# 2MB_Simplified.net
KiCad netlist of a schematic drawn in EAGLE
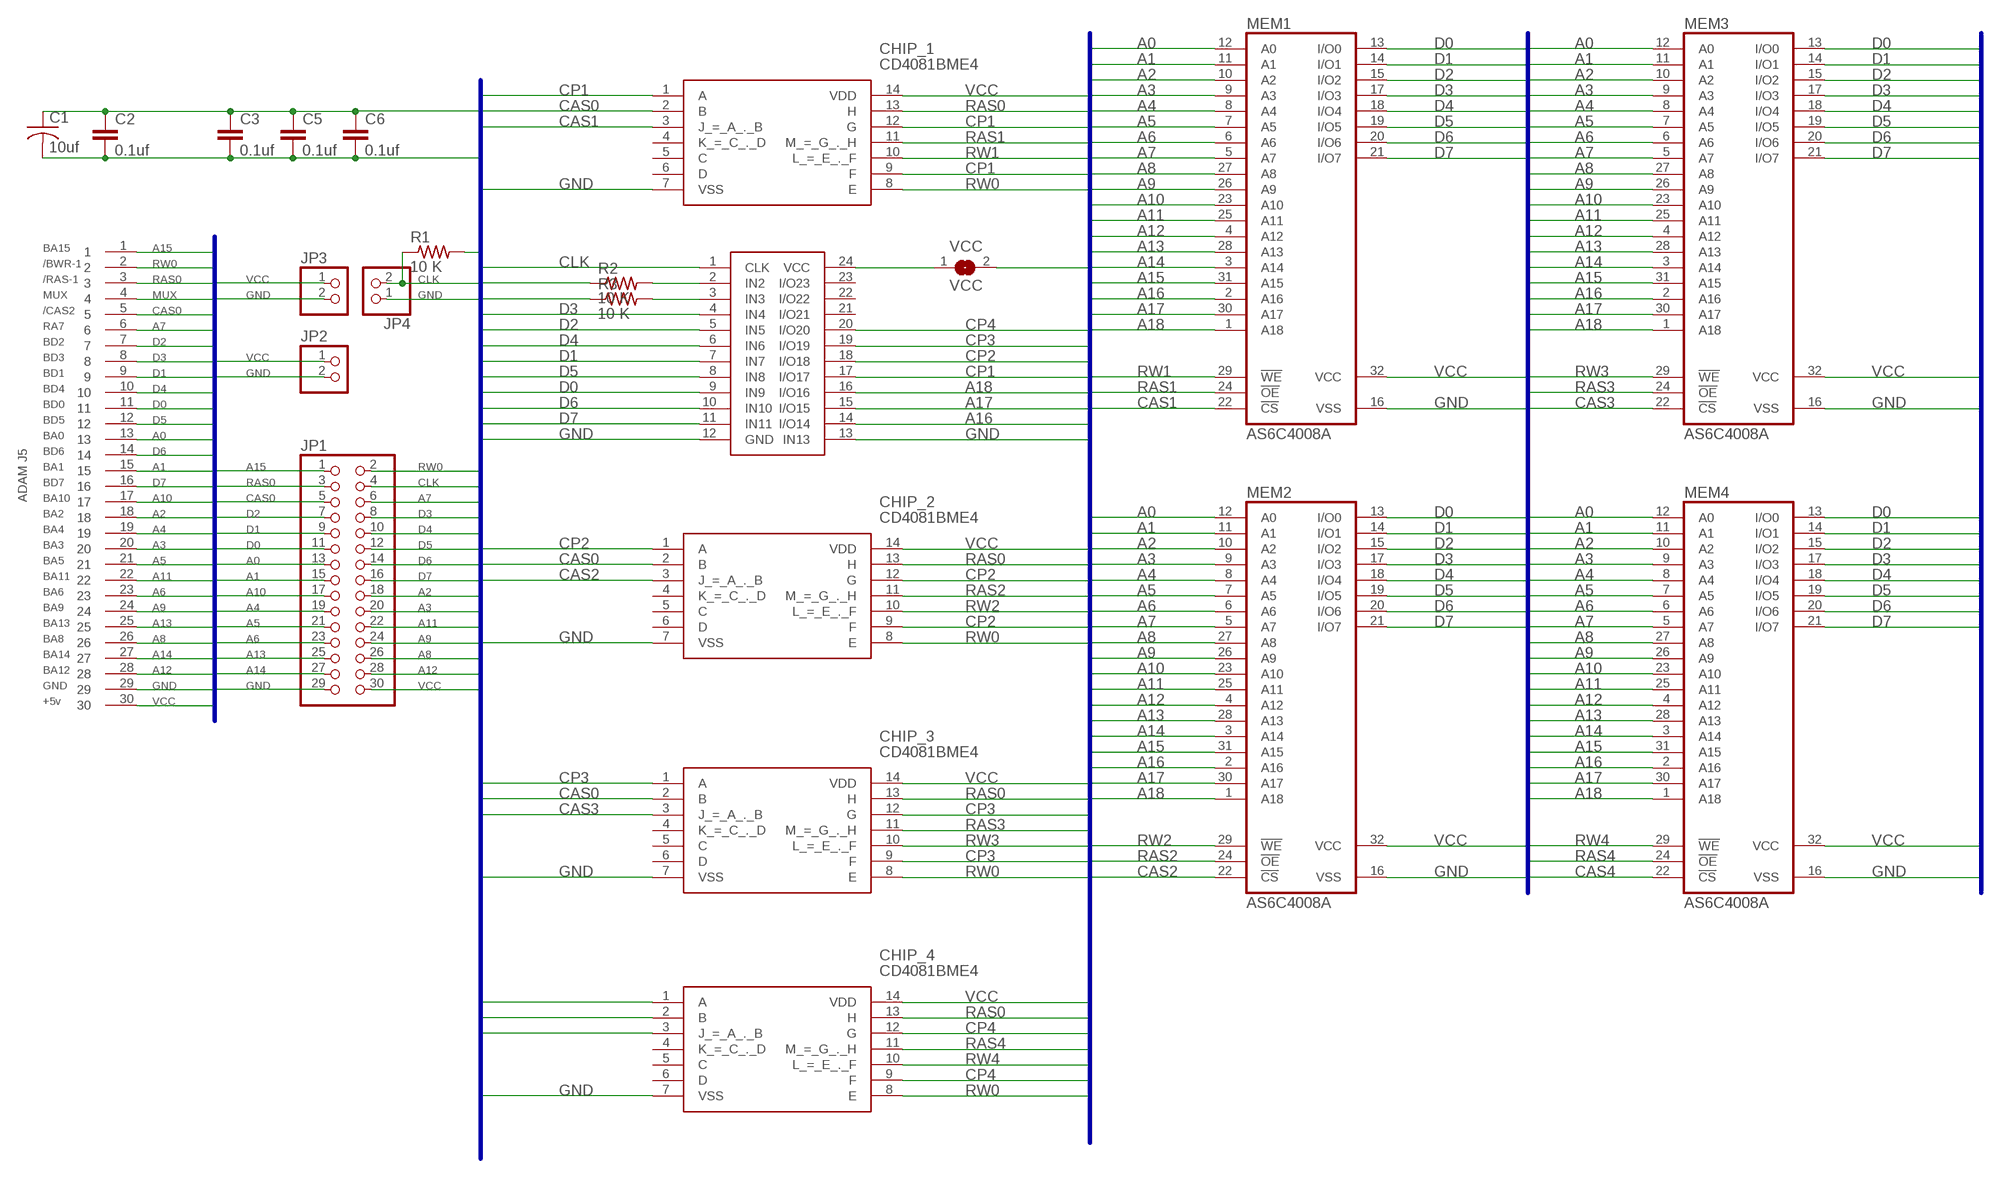
[diagram p0: schematic, sheet 1]

(export (version "E")
  (design (tool "Eeschema 10.0.6"))
  (components
    (comp (ref "C1")
      (value "10uf")
      (footprint "eagle-import:C050-025X075")
      (libsource (lib "eagle-import") (part "C-US050-025X075"))
    )
    (comp (ref "C2")
      (value "0.1uf")
      (footprint "eagle-import:C1206")
      (libsource (lib "eagle-import") (part "C-EUC1206"))
    )
    (comp (ref "C3")
      (value "0.1uf")
      (footprint "eagle-import:C1206")
      (libsource (lib "eagle-import") (part "C-EUC1206"))
    )
    (comp (ref "C5")
      (value "0.1uf")
      (footprint "eagle-import:C1206")
      (libsource (lib "eagle-import") (part "C-EUC1206"))
    )
    (comp (ref "C6")
      (value "0.1uf")
      (footprint "eagle-import:C1206")
      (libsource (lib "eagle-import") (part "C-EUC1206"))
    )
    (comp (ref "CHIP_1")
      (value "CD4081BME4")
      (footprint "eagle-import:SOIC127P600X175-14N")
      (fields (field (name "MOUSER_PART_NUMBER") "595-CD4081BME4"))
      (libsource (lib "eagle-import") (part "CD4081BME4"))
    )
    (comp (ref "CHIP_2")
      (value "CD4081BME4")
      (footprint "eagle-import:SOIC127P600X175-14N")
      (fields (field (name "MOUSER_PART_NUMBER") "595-CD4081BME4"))
      (libsource (lib "eagle-import") (part "CD4081BME4"))
    )
    (comp (ref "CHIP_3")
      (value "CD4081BME4")
      (footprint "eagle-import:SOIC127P600X175-14N")
      (fields (field (name "MOUSER_PART_NUMBER") "595-CD4081BME4"))
      (libsource (lib "eagle-import") (part "CD4081BME4"))
    )
    (comp (ref "CHIP_4")
      (value "CD4081BME4")
      (footprint "eagle-import:SOIC127P600X175-14N")
      (fields (field (name "MOUSER_PART_NUMBER") "595-CD4081BME4"))
      (libsource (lib "eagle-import") (part "CD4081BME4"))
    )
    (comp (ref "JP1")
      (value "PINHD-2X15")
      (footprint "eagle-import:2X15")
      (libsource (lib "eagle-import") (part "PINHD-2X15"))
    )
    (comp (ref "JP2")
      (value "PINHD-1X2")
      (footprint "eagle-import:1X02")
      (libsource (lib "eagle-import") (part "PINHD-1X2"))
    )
    (comp (ref "JP3")
      (value "PINHD-1X2")
      (footprint "eagle-import:1X02")
      (libsource (lib "eagle-import") (part "PINHD-1X2"))
    )
    (comp (ref "JP4")
      (value "PINHD-1X2")
      (footprint "eagle-import:1X02")
      (libsource (lib "eagle-import") (part "PINHD-1X2"))
    )
    (comp (ref "MEM1")
      (value "AS6C4008A")
      (footprint "eagle-import:SOP32-V2")
      (libsource (lib "eagle-import") (part "AS6C4008A"))
    )
    (comp (ref "MEM2")
      (value "AS6C4008A")
      (footprint "eagle-import:SOP32-V2")
      (libsource (lib "eagle-import") (part "AS6C4008A"))
    )
    (comp (ref "MEM3")
      (value "AS6C4008A")
      (footprint "eagle-import:SOP32-V2")
      (libsource (lib "eagle-import") (part "AS6C4008A"))
    )
    (comp (ref "MEM4")
      (value "AS6C4008A")
      (footprint "eagle-import:SOP32-V2")
      (libsource (lib "eagle-import") (part "AS6C4008A"))
    )
    (comp (ref "R1")
      (value "10 K")
      (footprint "eagle-import:M1206")
      (libsource (lib "eagle-import") (part "R-US_M1206"))
    )
    (comp (ref "R2")
      (value "10 K")
      (footprint "eagle-import:M1206")
      (libsource (lib "eagle-import") (part "R-US_M1206"))
    )
    (comp (ref "R3")
      (value "10 K")
      (footprint "eagle-import:M1206")
      (libsource (lib "eagle-import") (part "R-US_M1206"))
    )
    (comp (ref "U$3")
      (value "J5CARD")
      (footprint "eagle-import:J5CARD")
      (libsource (lib "eagle-import") (part "J5CARD"))
    )
    (comp (ref "U$6")
      (value "ATF22V10")
      (footprint "eagle-import:SO24W")
      (libsource (lib "eagle-import") (part "ATF22V10"))
    )
    (comp (ref "VCC")
      (value "VCC")
      (footprint "eagle-import:SJ")
      (libsource (lib "eagle-import") (part "SJ"))
    )
  )
  (nets
    (net (code "1") (name "/A0") (class "Default")
      (node (ref "JP1") (pin "13") (pinfunction "13_13") (pintype "passive"))
      (node (ref "MEM1") (pin "12") (pinfunction "A0_12") (pintype "input"))
      (node (ref "MEM2") (pin "12") (pinfunction "A0_12") (pintype "input"))
      (node (ref "MEM3") (pin "12") (pinfunction "A0_12") (pintype "input"))
      (node (ref "MEM4") (pin "12") (pinfunction "A0_12") (pintype "input"))
      (node (ref "U$3") (pin "13") (pinfunction "13_13") (pintype "bidirectional"))
    )
    (net (code "2") (name "/A1") (class "Default")
      (node (ref "JP1") (pin "15") (pinfunction "15_15") (pintype "passive"))
      (node (ref "MEM1") (pin "11") (pinfunction "A1_11") (pintype "input"))
      (node (ref "MEM2") (pin "11") (pinfunction "A1_11") (pintype "input"))
      (node (ref "MEM3") (pin "11") (pinfunction "A1_11") (pintype "input"))
      (node (ref "MEM4") (pin "11") (pinfunction "A1_11") (pintype "input"))
      (node (ref "U$3") (pin "15") (pinfunction "15_15") (pintype "bidirectional"))
    )
    (net (code "3") (name "/A2") (class "Default")
      (node (ref "JP1") (pin "18") (pinfunction "18_18") (pintype "passive"))
      (node (ref "MEM1") (pin "10") (pinfunction "A2_10") (pintype "input"))
      (node (ref "MEM2") (pin "10") (pinfunction "A2_10") (pintype "input"))
      (node (ref "MEM3") (pin "10") (pinfunction "A2_10") (pintype "input"))
      (node (ref "MEM4") (pin "10") (pinfunction "A2_10") (pintype "input"))
      (node (ref "U$3") (pin "18") (pinfunction "18_18") (pintype "bidirectional"))
    )
    (net (code "4") (name "/A3") (class "Default")
      (node (ref "JP1") (pin "20") (pinfunction "20_20") (pintype "passive"))
      (node (ref "MEM1") (pin "9") (pinfunction "A3_9") (pintype "input"))
      (node (ref "MEM2") (pin "9") (pinfunction "A3_9") (pintype "input"))
      (node (ref "MEM3") (pin "9") (pinfunction "A3_9") (pintype "input"))
      (node (ref "MEM4") (pin "9") (pinfunction "A3_9") (pintype "input"))
      (node (ref "U$3") (pin "20") (pinfunction "20_20") (pintype "bidirectional"))
    )
    (net (code "5") (name "/A4") (class "Default")
      (node (ref "JP1") (pin "19") (pinfunction "19_19") (pintype "passive"))
      (node (ref "MEM1") (pin "8") (pinfunction "A4_8") (pintype "input"))
      (node (ref "MEM2") (pin "8") (pinfunction "A4_8") (pintype "input"))
      (node (ref "MEM3") (pin "8") (pinfunction "A4_8") (pintype "input"))
      (node (ref "MEM4") (pin "8") (pinfunction "A4_8") (pintype "input"))
      (node (ref "U$3") (pin "19") (pinfunction "19_19") (pintype "bidirectional"))
    )
    (net (code "6") (name "/A5") (class "Default")
      (node (ref "JP1") (pin "21") (pinfunction "21_21") (pintype "passive"))
      (node (ref "MEM1") (pin "7") (pinfunction "A5_7") (pintype "input"))
      (node (ref "MEM2") (pin "7") (pinfunction "A5_7") (pintype "input"))
      (node (ref "MEM3") (pin "7") (pinfunction "A5_7") (pintype "input"))
      (node (ref "MEM4") (pin "7") (pinfunction "A5_7") (pintype "input"))
      (node (ref "U$3") (pin "21") (pinfunction "21_21") (pintype "bidirectional"))
    )
    (net (code "7") (name "/A6") (class "Default")
      (node (ref "JP1") (pin "23") (pinfunction "23_23") (pintype "passive"))
      (node (ref "MEM1") (pin "6") (pinfunction "A6_6") (pintype "input"))
      (node (ref "MEM2") (pin "6") (pinfunction "A6_6") (pintype "input"))
      (node (ref "MEM3") (pin "6") (pinfunction "A6_6") (pintype "input"))
      (node (ref "MEM4") (pin "6") (pinfunction "A6_6") (pintype "input"))
      (node (ref "U$3") (pin "23") (pinfunction "23_23") (pintype "bidirectional"))
    )
    (net (code "8") (name "/A7") (class "Default")
      (node (ref "JP1") (pin "6") (pinfunction "6_6") (pintype "passive"))
      (node (ref "MEM1") (pin "5") (pinfunction "A7_5") (pintype "input"))
      (node (ref "MEM2") (pin "5") (pinfunction "A7_5") (pintype "input"))
      (node (ref "MEM3") (pin "5") (pinfunction "A7_5") (pintype "input"))
      (node (ref "MEM4") (pin "5") (pinfunction "A7_5") (pintype "input"))
      (node (ref "U$3") (pin "6") (pinfunction "6_6") (pintype "bidirectional"))
    )
    (net (code "9") (name "/A8") (class "Default")
      (node (ref "JP1") (pin "26") (pinfunction "26_26") (pintype "passive"))
      (node (ref "MEM1") (pin "27") (pinfunction "A8_27") (pintype "input"))
      (node (ref "MEM2") (pin "27") (pinfunction "A8_27") (pintype "input"))
      (node (ref "MEM3") (pin "27") (pinfunction "A8_27") (pintype "input"))
      (node (ref "MEM4") (pin "27") (pinfunction "A8_27") (pintype "input"))
      (node (ref "U$3") (pin "26") (pinfunction "26_26") (pintype "bidirectional"))
    )
    (net (code "10") (name "/A9") (class "Default")
      (node (ref "JP1") (pin "24") (pinfunction "24_24") (pintype "passive"))
      (node (ref "MEM1") (pin "26") (pinfunction "A9_26") (pintype "input"))
      (node (ref "MEM2") (pin "26") (pinfunction "A9_26") (pintype "input"))
      (node (ref "MEM3") (pin "26") (pinfunction "A9_26") (pintype "input"))
      (node (ref "MEM4") (pin "26") (pinfunction "A9_26") (pintype "input"))
      (node (ref "U$3") (pin "24") (pinfunction "24_24") (pintype "bidirectional"))
    )
    (net (code "11") (name "/A10") (class "Default")
      (node (ref "JP1") (pin "17") (pinfunction "17_17") (pintype "passive"))
      (node (ref "MEM1") (pin "23") (pinfunction "A10_23") (pintype "input"))
      (node (ref "MEM2") (pin "23") (pinfunction "A10_23") (pintype "input"))
      (node (ref "MEM3") (pin "23") (pinfunction "A10_23") (pintype "input"))
      (node (ref "MEM4") (pin "23") (pinfunction "A10_23") (pintype "input"))
      (node (ref "U$3") (pin "17") (pinfunction "17_17") (pintype "bidirectional"))
    )
    (net (code "12") (name "/A11") (class "Default")
      (node (ref "JP1") (pin "22") (pinfunction "22_22") (pintype "passive"))
      (node (ref "MEM1") (pin "25") (pinfunction "A11_25") (pintype "input"))
      (node (ref "MEM2") (pin "25") (pinfunction "A11_25") (pintype "input"))
      (node (ref "MEM3") (pin "25") (pinfunction "A11_25") (pintype "input"))
      (node (ref "MEM4") (pin "25") (pinfunction "A11_25") (pintype "input"))
      (node (ref "U$3") (pin "22") (pinfunction "22_22") (pintype "bidirectional"))
    )
    (net (code "13") (name "/A12") (class "Default")
      (node (ref "JP1") (pin "28") (pinfunction "28_28") (pintype "passive"))
      (node (ref "MEM1") (pin "4") (pinfunction "A12_4") (pintype "input"))
      (node (ref "MEM2") (pin "4") (pinfunction "A12_4") (pintype "input"))
      (node (ref "MEM3") (pin "4") (pinfunction "A12_4") (pintype "input"))
      (node (ref "MEM4") (pin "4") (pinfunction "A12_4") (pintype "input"))
      (node (ref "U$3") (pin "28") (pinfunction "28_28") (pintype "bidirectional"))
    )
    (net (code "14") (name "/A13") (class "Default")
      (node (ref "JP1") (pin "25") (pinfunction "25_25") (pintype "passive"))
      (node (ref "MEM1") (pin "28") (pinfunction "A13_28") (pintype "input"))
      (node (ref "MEM2") (pin "28") (pinfunction "A13_28") (pintype "input"))
      (node (ref "MEM3") (pin "28") (pinfunction "A13_28") (pintype "input"))
      (node (ref "MEM4") (pin "28") (pinfunction "A13_28") (pintype "input"))
      (node (ref "U$3") (pin "25") (pinfunction "25_25") (pintype "bidirectional"))
    )
    (net (code "15") (name "/A14") (class "Default")
      (node (ref "JP1") (pin "27") (pinfunction "27_27") (pintype "passive"))
      (node (ref "MEM1") (pin "3") (pinfunction "A14_3") (pintype "input"))
      (node (ref "MEM2") (pin "3") (pinfunction "A14_3") (pintype "input"))
      (node (ref "MEM3") (pin "3") (pinfunction "A14_3") (pintype "input"))
      (node (ref "MEM4") (pin "3") (pinfunction "A14_3") (pintype "input"))
      (node (ref "U$3") (pin "27") (pinfunction "27_27") (pintype "bidirectional"))
    )
    (net (code "16") (name "/A15") (class "Default")
      (node (ref "JP1") (pin "1") (pinfunction "1_1") (pintype "passive"))
      (node (ref "MEM1") (pin "31") (pinfunction "A15_31") (pintype "input"))
      (node (ref "MEM2") (pin "31") (pinfunction "A15_31") (pintype "input"))
      (node (ref "MEM3") (pin "31") (pinfunction "A15_31") (pintype "input"))
      (node (ref "MEM4") (pin "31") (pinfunction "A15_31") (pintype "input"))
      (node (ref "U$3") (pin "1") (pinfunction "1_1") (pintype "bidirectional"))
    )
    (net (code "17") (name "/A16") (class "Default")
      (node (ref "MEM1") (pin "2") (pinfunction "A16_2") (pintype "input"))
      (node (ref "MEM2") (pin "2") (pinfunction "A16_2") (pintype "input"))
      (node (ref "MEM3") (pin "2") (pinfunction "A16_2") (pintype "input"))
      (node (ref "MEM4") (pin "2") (pinfunction "A16_2") (pintype "input"))
      (node (ref "U$6") (pin "14") (pinfunction "I/O14_14") (pintype "bidirectional"))
    )
    (net (code "18") (name "/A17") (class "Default")
      (node (ref "MEM1") (pin "30") (pinfunction "A17_30") (pintype "input"))
      (node (ref "MEM2") (pin "30") (pinfunction "A17_30") (pintype "input"))
      (node (ref "MEM3") (pin "30") (pinfunction "A17_30") (pintype "input"))
      (node (ref "MEM4") (pin "30") (pinfunction "A17_30") (pintype "input"))
      (node (ref "U$6") (pin "15") (pinfunction "I/O15_15") (pintype "bidirectional"))
    )
    (net (code "19") (name "/A18") (class "Default")
      (node (ref "MEM1") (pin "1") (pinfunction "A18_1") (pintype "input"))
      (node (ref "MEM2") (pin "1") (pinfunction "A18_1") (pintype "input"))
      (node (ref "MEM3") (pin "1") (pinfunction "A18_1") (pintype "input"))
      (node (ref "MEM4") (pin "1") (pinfunction "A18_1") (pintype "input"))
      (node (ref "U$6") (pin "16") (pinfunction "I/O16_16") (pintype "bidirectional"))
    )
    (net (code "20") (name "/CAS0") (class "Default")
      (node (ref "CHIP_1") (pin "2") (pinfunction "B_2") (pintype "bidirectional"))
      (node (ref "CHIP_2") (pin "2") (pinfunction "B_2") (pintype "bidirectional"))
      (node (ref "CHIP_3") (pin "2") (pinfunction "B_2") (pintype "bidirectional"))
      (node (ref "CHIP_4") (pin "2") (pinfunction "B_2") (pintype "bidirectional"))
      (node (ref "JP1") (pin "5") (pinfunction "5_5") (pintype "passive"))
      (node (ref "U$3") (pin "5") (pinfunction "5_5") (pintype "bidirectional"))
    )
    (net (code "21") (name "/CAS1") (class "Default")
      (node (ref "CHIP_1") (pin "3") (pinfunction "J_=_A_._B_3") (pintype "bidirectional"))
      (node (ref "MEM1") (pin "22") (pinfunction "~{CS}_22") (pintype "input"))
    )
    (net (code "22") (name "/CAS2") (class "Default")
      (node (ref "CHIP_2") (pin "3") (pinfunction "J_=_A_._B_3") (pintype "bidirectional"))
      (node (ref "MEM2") (pin "22") (pinfunction "~{CS}_22") (pintype "input"))
    )
    (net (code "23") (name "/CAS3") (class "Default")
      (node (ref "CHIP_3") (pin "3") (pinfunction "J_=_A_._B_3") (pintype "bidirectional"))
      (node (ref "MEM3") (pin "22") (pinfunction "~{CS}_22") (pintype "input"))
    )
    (net (code "24") (name "/CAS4") (class "Default")
      (node (ref "CHIP_4") (pin "3") (pinfunction "J_=_A_._B_3") (pintype "bidirectional"))
      (node (ref "MEM4") (pin "22") (pinfunction "~{CS}_22") (pintype "input"))
    )
    (net (code "25") (name "/CLK") (class "Default")
      (node (ref "JP1") (pin "4") (pinfunction "4_4") (pintype "passive"))
      (node (ref "JP4") (pin "2") (pinfunction "2_2") (pintype "passive"))
      (node (ref "R1") (pin "1") (pinfunction "1_1") (pintype "passive"))
      (node (ref "U$6") (pin "1") (pinfunction "CLK_1") (pintype "bidirectional"))
    )
    (net (code "26") (name "/CP1") (class "Default")
      (node (ref "CHIP_1") (pin "1") (pinfunction "A_1") (pintype "bidirectional"))
      (node (ref "CHIP_1") (pin "12") (pinfunction "G_12") (pintype "bidirectional"))
      (node (ref "CHIP_1") (pin "9") (pinfunction "F_9") (pintype "bidirectional"))
      (node (ref "U$6") (pin "17") (pinfunction "I/O17_17") (pintype "bidirectional"))
    )
    (net (code "27") (name "/CP2") (class "Default")
      (node (ref "CHIP_2") (pin "1") (pinfunction "A_1") (pintype "bidirectional"))
      (node (ref "CHIP_2") (pin "12") (pinfunction "G_12") (pintype "bidirectional"))
      (node (ref "CHIP_2") (pin "9") (pinfunction "F_9") (pintype "bidirectional"))
      (node (ref "U$6") (pin "18") (pinfunction "I/O18_18") (pintype "bidirectional"))
    )
    (net (code "28") (name "/CP3") (class "Default")
      (node (ref "CHIP_3") (pin "1") (pinfunction "A_1") (pintype "bidirectional"))
      (node (ref "CHIP_3") (pin "12") (pinfunction "G_12") (pintype "bidirectional"))
      (node (ref "CHIP_3") (pin "9") (pinfunction "F_9") (pintype "bidirectional"))
      (node (ref "U$6") (pin "19") (pinfunction "I/O19_19") (pintype "bidirectional"))
    )
    (net (code "29") (name "/CP4") (class "Default")
      (node (ref "CHIP_4") (pin "1") (pinfunction "A_1") (pintype "bidirectional"))
      (node (ref "CHIP_4") (pin "12") (pinfunction "G_12") (pintype "bidirectional"))
      (node (ref "CHIP_4") (pin "9") (pinfunction "F_9") (pintype "bidirectional"))
      (node (ref "U$6") (pin "20") (pinfunction "I/O20_20") (pintype "bidirectional"))
    )
    (net (code "30") (name "/D0") (class "Default")
      (node (ref "JP1") (pin "11") (pinfunction "11_11") (pintype "passive"))
      (node (ref "MEM1") (pin "13") (pinfunction "I/O0_13") (pintype "bidirectional"))
      (node (ref "MEM2") (pin "13") (pinfunction "I/O0_13") (pintype "bidirectional"))
      (node (ref "MEM3") (pin "13") (pinfunction "I/O0_13") (pintype "bidirectional"))
      (node (ref "MEM4") (pin "13") (pinfunction "I/O0_13") (pintype "bidirectional"))
      (node (ref "U$3") (pin "11") (pinfunction "11_11") (pintype "bidirectional"))
      (node (ref "U$6") (pin "9") (pinfunction "IN9_9") (pintype "bidirectional"))
    )
    (net (code "31") (name "/D1") (class "Default")
      (node (ref "JP1") (pin "9") (pinfunction "9_9") (pintype "passive"))
      (node (ref "MEM1") (pin "14") (pinfunction "I/O1_14") (pintype "bidirectional"))
      (node (ref "MEM2") (pin "14") (pinfunction "I/O1_14") (pintype "bidirectional"))
      (node (ref "MEM3") (pin "14") (pinfunction "I/O1_14") (pintype "bidirectional"))
      (node (ref "MEM4") (pin "14") (pinfunction "I/O1_14") (pintype "bidirectional"))
      (node (ref "U$3") (pin "9") (pinfunction "9_9") (pintype "bidirectional"))
      (node (ref "U$6") (pin "7") (pinfunction "IN7_7") (pintype "bidirectional"))
    )
    (net (code "32") (name "/D2") (class "Default")
      (node (ref "JP1") (pin "7") (pinfunction "7_7") (pintype "passive"))
      (node (ref "MEM1") (pin "15") (pinfunction "I/O2_15") (pintype "bidirectional"))
      (node (ref "MEM2") (pin "15") (pinfunction "I/O2_15") (pintype "bidirectional"))
      (node (ref "MEM3") (pin "15") (pinfunction "I/O2_15") (pintype "bidirectional"))
      (node (ref "MEM4") (pin "15") (pinfunction "I/O2_15") (pintype "bidirectional"))
      (node (ref "U$3") (pin "7") (pinfunction "7_7") (pintype "bidirectional"))
      (node (ref "U$6") (pin "5") (pinfunction "IN5_5") (pintype "bidirectional"))
    )
    (net (code "33") (name "/D3") (class "Default")
      (node (ref "JP1") (pin "8") (pinfunction "8_8") (pintype "passive"))
      (node (ref "MEM1") (pin "17") (pinfunction "I/O3_17") (pintype "bidirectional"))
      (node (ref "MEM2") (pin "17") (pinfunction "I/O3_17") (pintype "bidirectional"))
      (node (ref "MEM3") (pin "17") (pinfunction "I/O3_17") (pintype "bidirectional"))
      (node (ref "MEM4") (pin "17") (pinfunction "I/O3_17") (pintype "bidirectional"))
      (node (ref "U$3") (pin "8") (pinfunction "8_8") (pintype "bidirectional"))
      (node (ref "U$6") (pin "4") (pinfunction "IN4_4") (pintype "bidirectional"))
    )
    (net (code "34") (name "/D4") (class "Default")
      (node (ref "JP1") (pin "10") (pinfunction "10_10") (pintype "passive"))
      (node (ref "MEM1") (pin "18") (pinfunction "I/O4_18") (pintype "bidirectional"))
      (node (ref "MEM2") (pin "18") (pinfunction "I/O4_18") (pintype "bidirectional"))
      (node (ref "MEM3") (pin "18") (pinfunction "I/O4_18") (pintype "bidirectional"))
      (node (ref "MEM4") (pin "18") (pinfunction "I/O4_18") (pintype "bidirectional"))
      (node (ref "U$3") (pin "10") (pinfunction "10_10") (pintype "bidirectional"))
      (node (ref "U$6") (pin "6") (pinfunction "IN6_6") (pintype "bidirectional"))
    )
    (net (code "35") (name "/D5") (class "Default")
      (node (ref "JP1") (pin "12") (pinfunction "12_12") (pintype "passive"))
      (node (ref "MEM1") (pin "19") (pinfunction "I/O5_19") (pintype "bidirectional"))
      (node (ref "MEM2") (pin "19") (pinfunction "I/O5_19") (pintype "bidirectional"))
      (node (ref "MEM3") (pin "19") (pinfunction "I/O5_19") (pintype "bidirectional"))
      (node (ref "MEM4") (pin "19") (pinfunction "I/O5_19") (pintype "bidirectional"))
      (node (ref "U$3") (pin "12") (pinfunction "12_12") (pintype "bidirectional"))
      (node (ref "U$6") (pin "8") (pinfunction "IN8_8") (pintype "bidirectional"))
    )
    (net (code "36") (name "/D6") (class "Default")
      (node (ref "JP1") (pin "14") (pinfunction "14_14") (pintype "passive"))
      (node (ref "MEM1") (pin "20") (pinfunction "I/O6_20") (pintype "bidirectional"))
      (node (ref "MEM2") (pin "20") (pinfunction "I/O6_20") (pintype "bidirectional"))
      (node (ref "MEM3") (pin "20") (pinfunction "I/O6_20") (pintype "bidirectional"))
      (node (ref "MEM4") (pin "20") (pinfunction "I/O6_20") (pintype "bidirectional"))
      (node (ref "U$3") (pin "14") (pinfunction "14_14") (pintype "bidirectional"))
      (node (ref "U$6") (pin "10") (pinfunction "IN10_10") (pintype "bidirectional"))
    )
    (net (code "37") (name "/D7") (class "Default")
      (node (ref "JP1") (pin "16") (pinfunction "16_16") (pintype "passive"))
      (node (ref "MEM1") (pin "21") (pinfunction "I/O7_21") (pintype "bidirectional"))
      (node (ref "MEM2") (pin "21") (pinfunction "I/O7_21") (pintype "bidirectional"))
      (node (ref "MEM3") (pin "21") (pinfunction "I/O7_21") (pintype "bidirectional"))
      (node (ref "MEM4") (pin "21") (pinfunction "I/O7_21") (pintype "bidirectional"))
      (node (ref "U$3") (pin "16") (pinfunction "16_16") (pintype "bidirectional"))
      (node (ref "U$6") (pin "11") (pinfunction "IN11_11") (pintype "bidirectional"))
    )
    (net (code "38") (name "/GND") (class "Default")
      (node (ref "C1") (pin "2") (pinfunction "2_2") (pintype "passive"))
      (node (ref "C2") (pin "2") (pinfunction "2_2") (pintype "passive"))
      (node (ref "C3") (pin "2") (pinfunction "2_2") (pintype "passive"))
      (node (ref "C5") (pin "2") (pinfunction "2_2") (pintype "passive"))
      (node (ref "C6") (pin "2") (pinfunction "2_2") (pintype "passive"))
      (node (ref "CHIP_1") (pin "7") (pinfunction "VSS_7") (pintype "bidirectional"))
      (node (ref "CHIP_2") (pin "7") (pinfunction "VSS_7") (pintype "bidirectional"))
      (node (ref "CHIP_3") (pin "7") (pinfunction "VSS_7") (pintype "bidirectional"))
      (node (ref "CHIP_4") (pin "7") (pinfunction "VSS_7") (pintype "bidirectional"))
      (node (ref "JP1") (pin "29") (pinfunction "29_29") (pintype "passive"))
      (node (ref "JP2") (pin "2") (pinfunction "2_2") (pintype "passive"))
      (node (ref "JP3") (pin "2") (pinfunction "2_2") (pintype "passive"))
      (node (ref "JP4") (pin "1") (pinfunction "1_1") (pintype "passive"))
      (node (ref "MEM1") (pin "16") (pinfunction "VSS_16") (pintype "power_in"))
      (node (ref "MEM2") (pin "16") (pinfunction "VSS_16") (pintype "power_in"))
      (node (ref "MEM3") (pin "16") (pinfunction "VSS_16") (pintype "power_in"))
      (node (ref "MEM4") (pin "16") (pinfunction "VSS_16") (pintype "power_in"))
      (node (ref "R1") (pin "2") (pinfunction "2_2") (pintype "passive"))
      (node (ref "R2") (pin "1") (pinfunction "1_1") (pintype "passive"))
      (node (ref "R3") (pin "1") (pinfunction "1_1") (pintype "passive"))
      (node (ref "U$3") (pin "29") (pinfunction "29_29") (pintype "bidirectional"))
      (node (ref "U$6") (pin "12") (pinfunction "GND_12") (pintype "bidirectional"))
      (node (ref "U$6") (pin "13") (pinfunction "IN13_13") (pintype "bidirectional"))
    )
    (net (code "39") (name "/MUX") (class "Default")
      (node (ref "U$3") (pin "4") (pinfunction "4_4") (pintype "bidirectional"))
    )
    (net (code "40") (name "/RAS0") (class "Default")
      (node (ref "CHIP_1") (pin "13") (pinfunction "H_13") (pintype "bidirectional"))
      (node (ref "CHIP_2") (pin "13") (pinfunction "H_13") (pintype "bidirectional"))
      (node (ref "CHIP_3") (pin "13") (pinfunction "H_13") (pintype "bidirectional"))
      (node (ref "CHIP_4") (pin "13") (pinfunction "H_13") (pintype "bidirectional"))
      (node (ref "JP1") (pin "3") (pinfunction "3_3") (pintype "passive"))
      (node (ref "U$3") (pin "3") (pinfunction "3_3") (pintype "bidirectional"))
    )
    (net (code "41") (name "/RAS1") (class "Default")
      (node (ref "CHIP_1") (pin "11") (pinfunction "M_=_G_._H_11") (pintype "bidirectional"))
      (node (ref "MEM1") (pin "24") (pinfunction "~{OE}_24") (pintype "input"))
    )
    (net (code "42") (name "/RAS2") (class "Default")
      (node (ref "CHIP_2") (pin "11") (pinfunction "M_=_G_._H_11") (pintype "bidirectional"))
      (node (ref "MEM2") (pin "24") (pinfunction "~{OE}_24") (pintype "input"))
    )
    (net (code "43") (name "/RAS3") (class "Default")
      (node (ref "CHIP_3") (pin "11") (pinfunction "M_=_G_._H_11") (pintype "bidirectional"))
      (node (ref "MEM3") (pin "24") (pinfunction "~{OE}_24") (pintype "input"))
    )
    (net (code "44") (name "/RAS4") (class "Default")
      (node (ref "CHIP_4") (pin "11") (pinfunction "M_=_G_._H_11") (pintype "bidirectional"))
      (node (ref "MEM4") (pin "24") (pinfunction "~{OE}_24") (pintype "input"))
    )
    (net (code "45") (name "/RW0") (class "Default")
      (node (ref "CHIP_1") (pin "8") (pinfunction "E_8") (pintype "bidirectional"))
      (node (ref "CHIP_2") (pin "8") (pinfunction "E_8") (pintype "bidirectional"))
      (node (ref "CHIP_3") (pin "8") (pinfunction "E_8") (pintype "bidirectional"))
      (node (ref "CHIP_4") (pin "8") (pinfunction "E_8") (pintype "bidirectional"))
      (node (ref "JP1") (pin "2") (pinfunction "2_2") (pintype "passive"))
      (node (ref "U$3") (pin "2") (pinfunction "2_2") (pintype "bidirectional"))
    )
    (net (code "46") (name "/RW1") (class "Default")
      (node (ref "CHIP_1") (pin "10") (pinfunction "L_=_E_._F_10") (pintype "bidirectional"))
      (node (ref "MEM1") (pin "29") (pinfunction "~{WE}_29") (pintype "input"))
    )
    (net (code "47") (name "/RW2") (class "Default")
      (node (ref "CHIP_2") (pin "10") (pinfunction "L_=_E_._F_10") (pintype "bidirectional"))
      (node (ref "MEM2") (pin "29") (pinfunction "~{WE}_29") (pintype "input"))
    )
    (net (code "48") (name "/RW3") (class "Default")
      (node (ref "CHIP_3") (pin "10") (pinfunction "L_=_E_._F_10") (pintype "bidirectional"))
      (node (ref "MEM3") (pin "29") (pinfunction "~{WE}_29") (pintype "input"))
    )
    (net (code "49") (name "/RW4") (class "Default")
      (node (ref "CHIP_4") (pin "10") (pinfunction "L_=_E_._F_10") (pintype "bidirectional"))
      (node (ref "MEM4") (pin "29") (pinfunction "~{WE}_29") (pintype "input"))
    )
    (net (code "50") (name "/VCC") (class "Default")
      (node (ref "C1") (pin "1") (pinfunction "1_1") (pintype "passive"))
      (node (ref "C2") (pin "1") (pinfunction "1_1") (pintype "passive"))
      (node (ref "C3") (pin "1") (pinfunction "1_1") (pintype "passive"))
      (node (ref "C5") (pin "1") (pinfunction "1_1") (pintype "passive"))
      (node (ref "C6") (pin "1") (pinfunction "1_1") (pintype "passive"))
      (node (ref "CHIP_1") (pin "14") (pinfunction "VDD_14") (pintype "bidirectional"))
      (node (ref "CHIP_2") (pin "14") (pinfunction "VDD_14") (pintype "bidirectional"))
      (node (ref "CHIP_3") (pin "14") (pinfunction "VDD_14") (pintype "bidirectional"))
      (node (ref "CHIP_4") (pin "14") (pinfunction "VDD_14") (pintype "bidirectional"))
      (node (ref "JP1") (pin "30") (pinfunction "30_30") (pintype "passive"))
      (node (ref "JP2") (pin "1") (pinfunction "1_1") (pintype "passive"))
      (node (ref "JP3") (pin "1") (pinfunction "1_1") (pintype "passive"))
      (node (ref "MEM1") (pin "32") (pinfunction "VCC_32") (pintype "power_in"))
      (node (ref "MEM2") (pin "32") (pinfunction "VCC_32") (pintype "power_in"))
      (node (ref "MEM3") (pin "32") (pinfunction "VCC_32") (pintype "power_in"))
      (node (ref "MEM4") (pin "32") (pinfunction "VCC_32") (pintype "power_in"))
      (node (ref "U$3") (pin "30") (pinfunction "30_30") (pintype "bidirectional"))
      (node (ref "VCC") (pin "2") (pinfunction "2_2") (pintype "passive"))
    )
    (net (code "52") (name "Net-(U$6-IN2)") (class "Default")
      (node (ref "R2") (pin "2") (pinfunction "2_2") (pintype "passive"))
      (node (ref "U$6") (pin "2") (pinfunction "IN2_2") (pintype "bidirectional"))
    )
    (net (code "53") (name "Net-(U$6-IN3)") (class "Default")
      (node (ref "R3") (pin "2") (pinfunction "2_2") (pintype "passive"))
      (node (ref "U$6") (pin "3") (pinfunction "IN3_3") (pintype "bidirectional"))
    )
    (net (code "54") (name "Net-(U$6-VCC)") (class "Default")
      (node (ref "U$6") (pin "24") (pinfunction "VCC_24") (pintype "bidirectional"))
      (node (ref "VCC") (pin "1") (pinfunction "1_1") (pintype "passive"))
    )
    (net (code "55") (name "unconnected-(CHIP_1-C-Pad5)") (class "Default")
      (node (ref "CHIP_1") (pin "5") (pinfunction "C_5") (pintype "bidirectional"))
    )
    (net (code "56") (name "unconnected-(CHIP_1-D-Pad6)") (class "Default")
      (node (ref "CHIP_1") (pin "6") (pinfunction "D_6") (pintype "bidirectional"))
    )
    (net (code "57") (name "unconnected-(CHIP_1-K_=_C_._D-Pad4)") (class "Default")
      (node (ref "CHIP_1") (pin "4") (pinfunction "K_=_C_._D_4") (pintype "bidirectional"))
    )
    (net (code "58") (name "unconnected-(CHIP_2-C-Pad5)") (class "Default")
      (node (ref "CHIP_2") (pin "5") (pinfunction "C_5") (pintype "bidirectional"))
    )
    (net (code "59") (name "unconnected-(CHIP_2-D-Pad6)") (class "Default")
      (node (ref "CHIP_2") (pin "6") (pinfunction "D_6") (pintype "bidirectional"))
    )
    (net (code "60") (name "unconnected-(CHIP_2-K_=_C_._D-Pad4)") (class "Default")
      (node (ref "CHIP_2") (pin "4") (pinfunction "K_=_C_._D_4") (pintype "bidirectional"))
    )
    (net (code "61") (name "unconnected-(CHIP_3-C-Pad5)") (class "Default")
      (node (ref "CHIP_3") (pin "5") (pinfunction "C_5") (pintype "bidirectional"))
    )
    (net (code "62") (name "unconnected-(CHIP_3-D-Pad6)") (class "Default")
      (node (ref "CHIP_3") (pin "6") (pinfunction "D_6") (pintype "bidirectional"))
    )
    (net (code "63") (name "unconnected-(CHIP_3-K_=_C_._D-Pad4)") (class "Default")
      (node (ref "CHIP_3") (pin "4") (pinfunction "K_=_C_._D_4") (pintype "bidirectional"))
    )
    (net (code "64") (name "unconnected-(CHIP_4-C-Pad5)") (class "Default")
      (node (ref "CHIP_4") (pin "5") (pinfunction "C_5") (pintype "bidirectional"))
    )
    (net (code "65") (name "unconnected-(CHIP_4-D-Pad6)") (class "Default")
      (node (ref "CHIP_4") (pin "6") (pinfunction "D_6") (pintype "bidirectional"))
    )
    (net (code "66") (name "unconnected-(CHIP_4-K_=_C_._D-Pad4)") (class "Default")
      (node (ref "CHIP_4") (pin "4") (pinfunction "K_=_C_._D_4") (pintype "bidirectional"))
    )
    (net (code "67") (name "unconnected-(U$6-I{slash}O21-Pad21)") (class "Default")
      (node (ref "U$6") (pin "21") (pinfunction "I/O21_21") (pintype "bidirectional"))
    )
    (net (code "68") (name "unconnected-(U$6-I{slash}O22-Pad22)") (class "Default")
      (node (ref "U$6") (pin "22") (pinfunction "I/O22_22") (pintype "bidirectional"))
    )
    (net (code "69") (name "unconnected-(U$6-I{slash}O23-Pad23)") (class "Default")
      (node (ref "U$6") (pin "23") (pinfunction "I/O23_23") (pintype "bidirectional"))
    )
  )
)
